# USB_Comms.net
KiCad netlist of a schematic drawn in Altium Designer
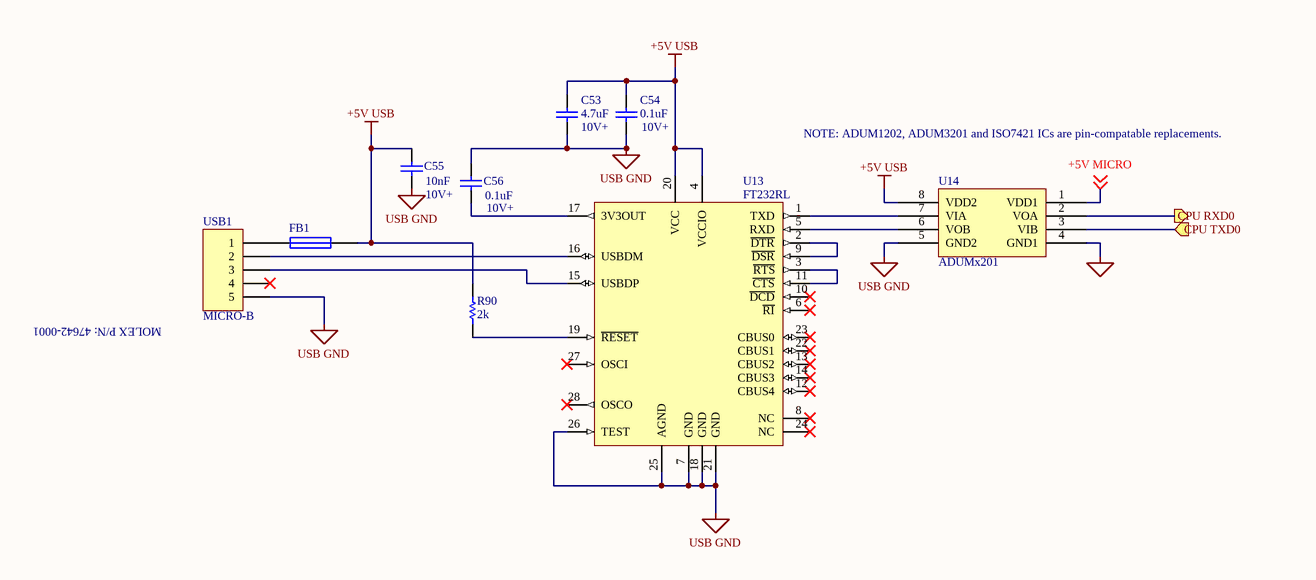
[diagram p0: USB Comms.SchDoc]

(export (version "E")
  (design (tool "Eeschema 10.0.6"))
  (components
    (comp (ref "C53")
      (value "4.7uF")
      (footprint "RAD-0.3")
      (description "Capacitor")
      (fields (field (name "PUBLISHER") "Altium Limited"))
      (libsource (lib "Miscellaneous Devices") (part "Cap"))
    )
    (comp (ref "C54")
      (value "0.1uF")
      (footprint "RAD-0.3")
      (description "Capacitor")
      (fields (field (name "PUBLISHER") "Altium Limited"))
      (libsource (lib "Miscellaneous Devices") (part "Cap"))
    )
    (comp (ref "C55")
      (value "10nF")
      (footprint "RAD-0.3")
      (description "Capacitor")
      (fields (field (name "PUBLISHER") "Altium Limited"))
      (libsource (lib "Miscellaneous Devices") (part "Cap"))
    )
    (comp (ref "C56")
      (value "0.1uF")
      (footprint "RAD-0.3")
      (description "Capacitor")
      (fields (field (name "PUBLISHER") "Altium Limited"))
      (libsource (lib "Miscellaneous Devices") (part "Cap"))
    )
    (comp (ref "FB1")
      (value "~")
      (footprint "PIN-W2/E2.8")
      (fields (field (name "PUBLISHER") "Altium Limited"))
      (libsource (lib "Miscellaneous Devices") (part "Fuse 1"))
    )
    (comp (ref "R90")
      (value "2k")
      (footprint "AXIAL-0.3")
      (description "Resistor")
      (fields (field (name "PUBLISHER") "Altium Limited"))
      (libsource (lib "Miscellaneous Devices") (part "Res1"))
    )
    (comp (ref "U13")
      (value "FT232RL")
      (footprint "SSOP-28_M")
      (description "USB UART Asynchronous Serial Data Transfer Chip, SSOP-28, Tray")
      (fields (field (name "PUBLISHER") "Altium Limited"))
      (libsource (lib "FTDI Communication UART") (part "FT232RL-Tray"))
    )
    (comp (ref "U14") (value "ADUMx201") (libsource (lib "FreeEMS Schematic Library") (part "ADUM3201")))
    (comp (ref "USB1")
      (value "MICRO-B")
      (footprint "HDR1X5")
      (description "Header, 5-Pin")
      (fields (field (name "PUBLISHER") "Altium Limited"))
      (libsource (lib "Miscellaneous Connectors") (part "Header 5"))
    )
  )
  (nets
    (net (code "1") (name "+5V MICRO") (class "Default")
      (node (ref "U14") (pin "1") (pinfunction "VDD1_1") (pintype "passive"))
    )
    (net (code "2") (name "+5V USB") (class "Default")
      (node (ref "C53") (pin "2") (pinfunction "2_2") (pintype "passive"))
      (node (ref "C54") (pin "2") (pinfunction "2_2") (pintype "passive"))
      (node (ref "C55") (pin "2") (pinfunction "2_2") (pintype "passive"))
      (node (ref "FB1") (pin "2") (pinfunction "2_2") (pintype "passive"))
      (node (ref "R90") (pin "2") (pinfunction "2_2") (pintype "passive"))
      (node (ref "U13") (pin "20") (pinfunction "VCC_20") (pintype "power_in"))
      (node (ref "U13") (pin "4") (pinfunction "VCCIO_4") (pintype "power_in"))
      (node (ref "U14") (pin "8") (pinfunction "VDD2_8") (pintype "passive"))
    )
    (net (code "3") (name "/CPU RXD0") (class "Default")
      (node (ref "U14") (pin "2") (pinfunction "VOA_2") (pintype "passive"))
    )
    (net (code "4") (name "/CPU TXD0") (class "Default")
      (node (ref "U14") (pin "3") (pinfunction "VIB_3") (pintype "passive"))
    )
    (net (code "5") (name "<NO NET>") (class "Default")
      (node (ref "U14") (pin "4") (pinfunction "GND1_4") (pintype "passive"))
    )
    (net (code "6") (name "Net-(U13-3V3OUT)") (class "Default")
      (node (ref "C56") (pin "1") (pinfunction "1_1") (pintype "passive"))
      (node (ref "U13") (pin "17") (pinfunction "3V3OUT_17") (pintype "output"))
    )
    (net (code "7") (name "Net-(U13-RXD)") (class "Default")
      (node (ref "U13") (pin "5") (pinfunction "RXD_5") (pintype "input"))
      (node (ref "U14") (pin "6") (pinfunction "VOB_6") (pintype "passive"))
    )
    (net (code "8") (name "Net-(U13-TXD)") (class "Default")
      (node (ref "U13") (pin "1") (pinfunction "TXD_1") (pintype "output"))
      (node (ref "U14") (pin "7") (pinfunction "VIA_7") (pintype "passive"))
    )
    (net (code "9") (name "Net-(U13-USBDM)") (class "Default")
      (node (ref "U13") (pin "16") (pinfunction "USBDM_16") (pintype "bidirectional"))
      (node (ref "USB1") (pin "2") (pinfunction "2_2") (pintype "passive"))
    )
    (net (code "10") (name "Net-(U13-USBDP)") (class "Default")
      (node (ref "U13") (pin "15") (pinfunction "USBDP_15") (pintype "bidirectional"))
      (node (ref "USB1") (pin "3") (pinfunction "3_3") (pintype "passive"))
    )
    (net (code "11") (name "Net-(U13-~{CTS})") (class "Default")
      (node (ref "U13") (pin "11") (pinfunction "~{CTS}_11") (pintype "input"))
      (node (ref "U13") (pin "3") (pinfunction "~{RTS}_3") (pintype "output"))
    )
    (net (code "12") (name "Net-(U13-~{DSR})") (class "Default")
      (node (ref "U13") (pin "2") (pinfunction "~{DTR}_2") (pintype "output"))
      (node (ref "U13") (pin "9") (pinfunction "~{DSR}_9") (pintype "input"))
    )
    (net (code "13") (name "Net-(U13-~{RESET})") (class "Default")
      (node (ref "R90") (pin "1") (pinfunction "1_1") (pintype "passive"))
      (node (ref "U13") (pin "19") (pinfunction "~{RESET}_19") (pintype "input"))
    )
    (net (code "14") (name "USB GND") (class "Default")
      (node (ref "C53") (pin "1") (pinfunction "1_1") (pintype "passive"))
      (node (ref "C54") (pin "1") (pinfunction "1_1") (pintype "passive"))
      (node (ref "C55") (pin "1") (pinfunction "1_1") (pintype "passive"))
      (node (ref "C56") (pin "2") (pinfunction "2_2") (pintype "passive"))
      (node (ref "U13") (pin "18") (pinfunction "GND_18") (pintype "power_in"))
      (node (ref "U13") (pin "21") (pinfunction "GND_21") (pintype "power_in"))
      (node (ref "U13") (pin "25") (pinfunction "AGND_25") (pintype "power_in"))
      (node (ref "U13") (pin "26") (pinfunction "TEST_26") (pintype "input"))
      (node (ref "U13") (pin "7") (pinfunction "GND_7") (pintype "power_in"))
      (node (ref "U14") (pin "5") (pinfunction "GND2_5") (pintype "passive"))
      (node (ref "USB1") (pin "5") (pinfunction "5_5") (pintype "passive"))
    )
    (net (code "15") (name "unconnected-(FB1-Pad1)") (class "Default")
      (node (ref "FB1") (pin "1") (pinfunction "1_1") (pintype "passive"))
    )
    (net (code "16") (name "unconnected-(U13-CBUS0-Pad23)") (class "Default")
      (node (ref "U13") (pin "23") (pinfunction "CBUS0_23") (pintype "bidirectional+no_connect"))
    )
    (net (code "17") (name "unconnected-(U13-CBUS1-Pad22)") (class "Default")
      (node (ref "U13") (pin "22") (pinfunction "CBUS1_22") (pintype "bidirectional+no_connect"))
    )
    (net (code "18") (name "unconnected-(U13-CBUS2-Pad13)") (class "Default")
      (node (ref "U13") (pin "13") (pinfunction "CBUS2_13") (pintype "bidirectional+no_connect"))
    )
    (net (code "19") (name "unconnected-(U13-CBUS3-Pad14)") (class "Default")
      (node (ref "U13") (pin "14") (pinfunction "CBUS3_14") (pintype "bidirectional+no_connect"))
    )
    (net (code "20") (name "unconnected-(U13-CBUS4-Pad12)") (class "Default")
      (node (ref "U13") (pin "12") (pinfunction "CBUS4_12") (pintype "bidirectional+no_connect"))
    )
    (net (code "21") (name "unconnected-(U13-NC-Pad8)") (class "Default")
      (node (ref "U13") (pin "8") (pinfunction "NC_8") (pintype "passive+no_connect"))
    )
    (net (code "22") (name "unconnected-(U13-NC-Pad24)") (class "Default")
      (node (ref "U13") (pin "24") (pinfunction "NC_24") (pintype "passive+no_connect"))
    )
    (net (code "23") (name "unconnected-(U13-OSCI-Pad27)") (class "Default")
      (node (ref "U13") (pin "27") (pinfunction "OSCI_27") (pintype "input+no_connect"))
    )
    (net (code "24") (name "unconnected-(U13-OSCO-Pad28)") (class "Default")
      (node (ref "U13") (pin "28") (pinfunction "OSCO_28") (pintype "output+no_connect"))
    )
    (net (code "25") (name "unconnected-(U13-~{DCD}-Pad10)") (class "Default")
      (node (ref "U13") (pin "10") (pinfunction "~{DCD}_10") (pintype "input+no_connect"))
    )
    (net (code "26") (name "unconnected-(U13-~{RI}-Pad6)") (class "Default")
      (node (ref "U13") (pin "6") (pinfunction "~{RI}_6") (pintype "input+no_connect"))
    )
    (net (code "27") (name "unconnected-(USB1-Pad1)") (class "Default")
      (node (ref "USB1") (pin "1") (pinfunction "1_1") (pintype "passive"))
    )
    (net (code "28") (name "unconnected-(USB1-Pad4)") (class "Default")
      (node (ref "USB1") (pin "4") (pinfunction "4_4") (pintype "passive+no_connect"))
    )
  )
)
